# yksb.net
KiCad netlist of a schematic drawn in Altium Designer
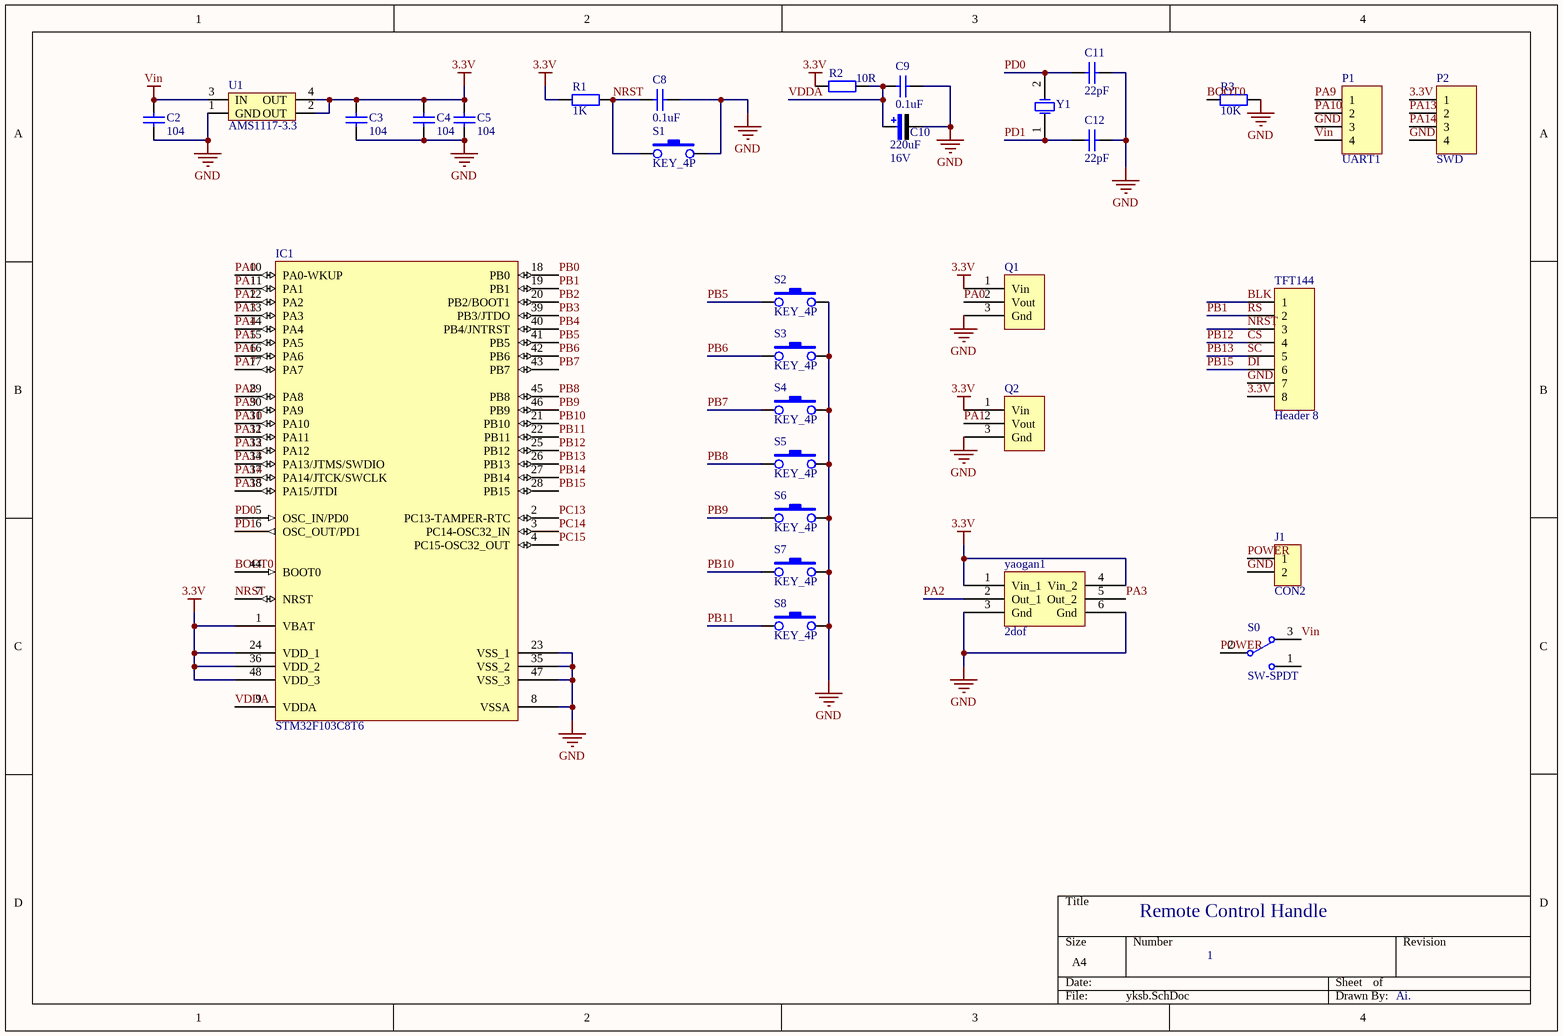
[diagram p0: yksb.SchDoc]

(export (version "E")
  (design (tool "Eeschema 10.0.6"))
  (components
    (comp (ref "C2")
      (value "104")
      (footprint "C-RAD-0603")
      (description "无极性电容")
      (fields (field (name "Comment") "Cap") (field (name "PUBLISHER") "Altium Limited"))
      (libsource (lib "Fszhang") (part "Cap"))
    )
    (comp (ref "C3")
      (value "104")
      (footprint "C-RAD-0603")
      (description "无极性电容")
      (fields (field (name "Comment") "Cap") (field (name "PUBLISHER") "Altium Limited"))
      (libsource (lib "Fszhang") (part "Cap"))
    )
    (comp (ref "C4")
      (value "104")
      (footprint "C-RAD-0603")
      (description "无极性电容")
      (fields (field (name "Comment") "Cap") (field (name "PUBLISHER") "Altium Limited"))
      (libsource (lib "Fszhang") (part "Cap"))
    )
    (comp (ref "C5")
      (value "104")
      (footprint "C-RAD-0603")
      (description "无极性电容")
      (fields (field (name "Comment") "Cap") (field (name "PUBLISHER") "Altium Limited"))
      (libsource (lib "Fszhang") (part "Cap"))
    )
    (comp (ref "C8")
      (value "0.1uF")
      (footprint "C-RAD-0603")
      (description "无极性电容")
      (fields (field (name "Comment") "Cap") (field (name "PUBLISHER") "Altium Limited"))
      (libsource (lib "Fszhang") (part "Cap"))
    )
    (comp (ref "C9")
      (value "0.1uF")
      (footprint "C-RAD-0603")
      (description "无极性电容")
      (fields (field (name "Comment") "Cap") (field (name "PUBLISHER") "Altium Limited"))
      (libsource (lib "Fszhang") (part "Cap"))
    )
    (comp (ref "C10")
      (value "220uF")
      (footprint "C-RB-S6")
      (description "极性电解电容")
      (fields
        (field (name "VOL") "16V")
        (field (name "Comment") "Cap Pol")
        (field (name "PUBLISHER") "Altium Limited")
      )
      (libsource (lib "Fszhang") (part "Cap Pol"))
    )
    (comp (ref "C11")
      (value "22pF")
      (footprint "C-RAD-0603")
      (description "无极性电容")
      (fields (field (name "Comment") "Cap") (field (name "PUBLISHER") "Altium Limited"))
      (libsource (lib "Fszhang") (part "Cap"))
    )
    (comp (ref "C12")
      (value "22pF")
      (footprint "C-RAD-0603")
      (description "无极性电容")
      (fields (field (name "Comment") "Cap") (field (name "PUBLISHER") "Altium Limited"))
      (libsource (lib "Fszhang") (part "Cap"))
    )
    (comp (ref "IC1")
      (value "STM32F103C8T6")
      (footprint "LQFP48_M")
      (description "单片机")
      (fields (field (name "PUBLISHER") "Altium Limited"))
      (libsource (lib "Chip") (part "STM32F103C8T6"))
    )
    (comp (ref "J1")
      (value "CON2")
      (footprint "DC-005")
      (description "连接器")
      (libsource (lib "Connector") (part "CON2"))
    )
    (comp (ref "P1")
      (value "UART1")
      (footprint "HDR1X4")
      (description "Header, 4-Pin")
      (fields (field (name "PUBLISHER") "Altium Limited"))
      (libsource (lib "Miscellaneous Connectors") (part "Header 4"))
    )
    (comp (ref "P2")
      (value "SWD")
      (footprint "HDR1X4")
      (description "Header, 4-Pin")
      (fields (field (name "PUBLISHER") "Altium Limited"))
      (libsource (lib "Miscellaneous Connectors") (part "Header 4"))
    )
    (comp (ref "Q1") (value "~") (footprint "dianweiqi") (libsource (lib "yaogan1") (part "dianweiqi")))
    (comp (ref "Q2") (value "~") (footprint "dianweiqi") (libsource (lib "yaogan1") (part "dianweiqi")))
    (comp (ref "R1")
      (value "1K")
      (footprint "0603-1")
      (description "贴片电阻")
      (fields (field (name "Comment") "Res1") (field (name "PUBLISHER") "Altium Limited"))
      (libsource (lib "Fszhang") (part "Res1"))
    )
    (comp (ref "R2")
      (value "10R")
      (footprint "0603-1")
      (description "贴片电阻")
      (fields (field (name "Comment") "Res1") (field (name "PUBLISHER") "Altium Limited"))
      (libsource (lib "Fszhang") (part "Res1"))
    )
    (comp (ref "R3")
      (value "10K")
      (footprint "0603-1")
      (description "贴片电阻")
      (fields (field (name "Comment") "Res1") (field (name "PUBLISHER") "Altium Limited"))
      (libsource (lib "Fszhang") (part "Res1"))
    )
    (comp (ref "S0")
      (value "SW-SPDT")
      (footprint "SWITCH_A2")
      (description "开关")
      (fields (field (name "PUBLISHER") "Altium Limited"))
      (libsource (lib "Fszhang") (part "SW-SPDT"))
    )
    (comp (ref "S1")
      (value "KEY_4P")
      (footprint "KEY_M")
      (description "轻触按键4P")
      (libsource (lib "Component") (part "KEY_4P"))
    )
    (comp (ref "S2")
      (value "KEY_4P")
      (footprint "KEY_M")
      (description "轻触按键4P")
      (libsource (lib "Component") (part "KEY_4P"))
    )
    (comp (ref "S3")
      (value "KEY_4P")
      (footprint "KEY_M")
      (description "轻触按键4P")
      (libsource (lib "Component") (part "KEY_4P"))
    )
    (comp (ref "S4")
      (value "KEY_4P")
      (footprint "KEY_M")
      (description "轻触按键4P")
      (libsource (lib "Component") (part "KEY_4P"))
    )
    (comp (ref "S5")
      (value "KEY_4P")
      (footprint "KEY_M")
      (description "轻触按键4P")
      (libsource (lib "Component") (part "KEY_4P"))
    )
    (comp (ref "S6")
      (value "KEY_4P")
      (footprint "KEY_M")
      (description "轻触按键4P")
      (libsource (lib "Component") (part "KEY_4P"))
    )
    (comp (ref "S7")
      (value "KEY_4P")
      (footprint "KEY_M")
      (description "轻触按键4P")
      (libsource (lib "Component") (part "KEY_4P"))
    )
    (comp (ref "S8")
      (value "KEY_4P")
      (footprint "KEY_M")
      (description "轻触按键4P")
      (libsource (lib "Component") (part "KEY_4P"))
    )
    (comp (ref "TFT144")
      (value "Header 8")
      (footprint "HDR1X8")
      (description "Header, 8-Pin")
      (fields (field (name "PUBLISHER") "Altium Limited"))
      (libsource (lib "Miscellaneous Connectors") (part "Header 8"))
    )
    (comp (ref "U1")
      (value "AMS1117-3.3")
      (footprint "AMS1117")
      (libsource (lib "MiniSTM32 V3.0封装库") (part "AMS1117"))
    )
    (comp (ref "Y1")
      (value "XTAL")
      (footprint "XTAL_US")
      (description "Crystal Oscillator")
      (fields (field (name "PUBLISHER") "*"))
      (libsource (lib "MiniSTM32底板_SCH (1)") (part "XTAL"))
    )
    (comp (ref "yaogan1") (value "2dof") (footprint "yaogan1") (libsource (lib "yaogan1") (part "yaogan1")))
  )
  (nets
    (net (code "1") (name "/BLK") (class "Default")
      (node (ref "TFT144") (pin "1") (pinfunction "1_1") (pintype "passive"))
    )
    (net (code "2") (name "/BOOT0") (class "Default")
      (node (ref "IC1") (pin "44") (pinfunction "BOOT0_44") (pintype "input"))
      (node (ref "R3") (pin "1") (pinfunction "1_1") (pintype "passive"))
    )
    (net (code "3") (name "/CS") (class "Default")
      (node (ref "IC1") (pin "25") (pinfunction "PB12_25") (pintype "bidirectional"))
      (node (ref "TFT144") (pin "4") (pinfunction "4_4") (pintype "passive"))
    )
    (net (code "4") (name "/DI") (class "Default")
      (node (ref "IC1") (pin "28") (pinfunction "PB15_28") (pintype "bidirectional"))
      (node (ref "TFT144") (pin "6") (pinfunction "6_6") (pintype "passive"))
    )
    (net (code "5") (name "/NRST") (class "Default")
      (node (ref "C8") (pin "2") (pinfunction "2_2") (pintype "passive"))
      (node (ref "IC1") (pin "7") (pinfunction "NRST_7") (pintype "bidirectional"))
      (node (ref "R1") (pin "2") (pinfunction "2_2") (pintype "passive"))
      (node (ref "S1") (pin "1") (pinfunction "1_1") (pintype "passive"))
      (node (ref "TFT144") (pin "3") (pinfunction "3_3") (pintype "passive"))
    )
    (net (code "6") (name "/PA0") (class "Default")
      (node (ref "IC1") (pin "10") (pinfunction "PA0-WKUP_10") (pintype "bidirectional"))
      (node (ref "Q1") (pin "2") (pinfunction "Vout_2") (pintype "passive"))
    )
    (net (code "7") (name "/PA1") (class "Default")
      (node (ref "IC1") (pin "11") (pinfunction "PA1_11") (pintype "bidirectional"))
      (node (ref "Q2") (pin "2") (pinfunction "Vout_2") (pintype "passive"))
    )
    (net (code "8") (name "/PA2") (class "Default")
      (node (ref "IC1") (pin "12") (pinfunction "PA2_12") (pintype "bidirectional"))
      (node (ref "yaogan1") (pin "2") (pinfunction "Out_1_2") (pintype "passive"))
    )
    (net (code "9") (name "/PA3") (class "Default")
      (node (ref "IC1") (pin "13") (pinfunction "PA3_13") (pintype "bidirectional"))
      (node (ref "yaogan1") (pin "5") (pinfunction "Out_2_5") (pintype "passive"))
    )
    (net (code "10") (name "/PA4") (class "Default")
      (node (ref "IC1") (pin "14") (pinfunction "PA4_14") (pintype "bidirectional"))
    )
    (net (code "11") (name "/PA5") (class "Default")
      (node (ref "IC1") (pin "15") (pinfunction "PA5_15") (pintype "bidirectional"))
    )
    (net (code "12") (name "/PA6") (class "Default")
      (node (ref "IC1") (pin "16") (pinfunction "PA6_16") (pintype "bidirectional"))
    )
    (net (code "13") (name "/PA7") (class "Default")
      (node (ref "IC1") (pin "17") (pinfunction "PA7_17") (pintype "bidirectional"))
    )
    (net (code "14") (name "/PA8") (class "Default")
      (node (ref "IC1") (pin "29") (pinfunction "PA8_29") (pintype "bidirectional"))
    )
    (net (code "15") (name "/PA9") (class "Default")
      (node (ref "IC1") (pin "30") (pinfunction "PA9_30") (pintype "bidirectional"))
      (node (ref "P1") (pin "1") (pinfunction "1_1") (pintype "passive"))
    )
    (net (code "16") (name "/PA10") (class "Default")
      (node (ref "IC1") (pin "31") (pinfunction "PA10_31") (pintype "bidirectional"))
      (node (ref "P1") (pin "2") (pinfunction "2_2") (pintype "passive"))
    )
    (net (code "17") (name "/PA11") (class "Default")
      (node (ref "IC1") (pin "32") (pinfunction "PA11_32") (pintype "bidirectional"))
    )
    (net (code "18") (name "/PA12") (class "Default")
      (node (ref "IC1") (pin "33") (pinfunction "PA12_33") (pintype "bidirectional"))
    )
    (net (code "19") (name "/PA13") (class "Default")
      (node (ref "IC1") (pin "34") (pinfunction "PA13/JTMS/SWDIO_34") (pintype "bidirectional"))
      (node (ref "P2") (pin "2") (pinfunction "2_2") (pintype "passive"))
    )
    (net (code "20") (name "/PA14") (class "Default")
      (node (ref "IC1") (pin "37") (pinfunction "PA14/JTCK/SWCLK_37") (pintype "bidirectional"))
      (node (ref "P2") (pin "3") (pinfunction "3_3") (pintype "passive"))
    )
    (net (code "21") (name "/PA15") (class "Default")
      (node (ref "IC1") (pin "38") (pinfunction "PA15/JTDI_38") (pintype "bidirectional"))
    )
    (net (code "22") (name "/PB0") (class "Default")
      (node (ref "IC1") (pin "18") (pinfunction "PB0_18") (pintype "bidirectional"))
    )
    (net (code "23") (name "/PB1") (class "Default")
      (node (ref "IC1") (pin "19") (pinfunction "PB1_19") (pintype "bidirectional"))
      (node (ref "TFT144") (pin "2") (pinfunction "2_2") (pintype "passive"))
    )
    (net (code "24") (name "/PB2") (class "Default")
      (node (ref "IC1") (pin "20") (pinfunction "PB2/BOOT1_20") (pintype "bidirectional"))
    )
    (net (code "25") (name "/PB3") (class "Default")
      (node (ref "IC1") (pin "39") (pinfunction "PB3/JTDO_39") (pintype "bidirectional"))
    )
    (net (code "26") (name "/PB4") (class "Default")
      (node (ref "IC1") (pin "40") (pinfunction "PB4/JNTRST_40") (pintype "bidirectional"))
    )
    (net (code "27") (name "/PB5") (class "Default")
      (node (ref "IC1") (pin "41") (pinfunction "PB5_41") (pintype "bidirectional"))
      (node (ref "S2") (pin "1") (pinfunction "1_1") (pintype "passive"))
    )
    (net (code "28") (name "/PB6") (class "Default")
      (node (ref "IC1") (pin "42") (pinfunction "PB6_42") (pintype "bidirectional"))
      (node (ref "S3") (pin "1") (pinfunction "1_1") (pintype "passive"))
    )
    (net (code "29") (name "/PB7") (class "Default")
      (node (ref "IC1") (pin "43") (pinfunction "PB7_43") (pintype "bidirectional"))
      (node (ref "S4") (pin "1") (pinfunction "1_1") (pintype "passive"))
    )
    (net (code "30") (name "/PB8") (class "Default")
      (node (ref "IC1") (pin "45") (pinfunction "PB8_45") (pintype "bidirectional"))
      (node (ref "S5") (pin "1") (pinfunction "1_1") (pintype "passive"))
    )
    (net (code "31") (name "/PB9") (class "Default")
      (node (ref "IC1") (pin "46") (pinfunction "PB9_46") (pintype "bidirectional"))
      (node (ref "S6") (pin "1") (pinfunction "1_1") (pintype "passive"))
    )
    (net (code "32") (name "/PB10") (class "Default")
      (node (ref "IC1") (pin "21") (pinfunction "PB10_21") (pintype "bidirectional"))
      (node (ref "S7") (pin "1") (pinfunction "1_1") (pintype "passive"))
    )
    (net (code "33") (name "/PB11") (class "Default")
      (node (ref "IC1") (pin "22") (pinfunction "PB11_22") (pintype "bidirectional"))
      (node (ref "S8") (pin "1") (pinfunction "1_1") (pintype "passive"))
    )
    (net (code "34") (name "/PB13") (class "Default")
      (node (ref "IC1") (pin "26") (pinfunction "PB13_26") (pintype "bidirectional"))
      (node (ref "TFT144") (pin "5") (pinfunction "5_5") (pintype "passive"))
    )
    (net (code "35") (name "/PB14") (class "Default")
      (node (ref "IC1") (pin "27") (pinfunction "PB14_27") (pintype "bidirectional"))
    )
    (net (code "36") (name "/PC13") (class "Default")
      (node (ref "IC1") (pin "2") (pinfunction "PC13-TAMPER-RTC_2") (pintype "bidirectional"))
    )
    (net (code "37") (name "/PC14") (class "Default")
      (node (ref "IC1") (pin "3") (pinfunction "PC14-OSC32_IN_3") (pintype "bidirectional"))
    )
    (net (code "38") (name "/PC15") (class "Default")
      (node (ref "IC1") (pin "4") (pinfunction "PC15-OSC32_OUT_4") (pintype "bidirectional"))
    )
    (net (code "39") (name "/PD0") (class "Default")
      (node (ref "C11") (pin "1") (pinfunction "1_1") (pintype "passive"))
      (node (ref "IC1") (pin "5") (pinfunction "OSC_IN/PD0_5") (pintype "input"))
      (node (ref "Y1") (pin "2") (pinfunction "OSC2_2") (pintype "passive"))
    )
    (net (code "40") (name "/PD1") (class "Default")
      (node (ref "C12") (pin "1") (pinfunction "1_1") (pintype "passive"))
      (node (ref "IC1") (pin "6") (pinfunction "OSC_OUT/PD1_6") (pintype "output"))
      (node (ref "Y1") (pin "1") (pinfunction "OSC1_1") (pintype "passive"))
    )
    (net (code "41") (name "/POWER") (class "Default")
      (node (ref "J1") (pin "1") (pinfunction "1_1") (pintype "passive"))
      (node (ref "S0") (pin "2") (pinfunction "2_2") (pintype "passive"))
    )
    (net (code "42") (name "/VDDA") (class "Default")
      (node (ref "C10") (pin "1") (pinfunction "1_1") (pintype "passive"))
      (node (ref "C9") (pin "2") (pinfunction "2_2") (pintype "passive"))
      (node (ref "IC1") (pin "9") (pinfunction "VDDA_9") (pintype "power_in"))
      (node (ref "R2") (pin "2") (pinfunction "2_2") (pintype "passive"))
    )
    (net (code "43") (name "3.3V") (class "Default")
      (node (ref "C3") (pin "1") (pinfunction "1_1") (pintype "passive"))
      (node (ref "C4") (pin "1") (pinfunction "1_1") (pintype "passive"))
      (node (ref "C5") (pin "1") (pinfunction "1_1") (pintype "passive"))
      (node (ref "IC1") (pin "1") (pinfunction "VBAT_1") (pintype "power_in"))
      (node (ref "IC1") (pin "24") (pinfunction "VDD_1_24") (pintype "power_in"))
      (node (ref "IC1") (pin "36") (pinfunction "VDD_2_36") (pintype "power_in"))
      (node (ref "IC1") (pin "48") (pinfunction "VDD_3_48") (pintype "power_in"))
      (node (ref "P2") (pin "1") (pinfunction "1_1") (pintype "passive"))
      (node (ref "Q1") (pin "1") (pinfunction "Vin_1") (pintype "passive"))
      (node (ref "Q2") (pin "1") (pinfunction "Vin_1") (pintype "passive"))
      (node (ref "R1") (pin "1") (pinfunction "1_1") (pintype "passive"))
      (node (ref "R2") (pin "1") (pinfunction "1_1") (pintype "passive"))
      (node (ref "TFT144") (pin "8") (pinfunction "8_8") (pintype "passive"))
      (node (ref "U1") (pin "2") (pinfunction "OUT_2") (pintype "passive"))
      (node (ref "U1") (pin "4") (pinfunction "OUT_4") (pintype "passive"))
      (node (ref "yaogan1") (pin "1") (pinfunction "Vin_1_1") (pintype "passive"))
      (node (ref "yaogan1") (pin "4") (pinfunction "Vin_2_4") (pintype "passive"))
    )
    (net (code "44") (name "GND") (class "Default")
      (node (ref "C10") (pin "2") (pinfunction "2_2") (pintype "passive"))
      (node (ref "C11") (pin "2") (pinfunction "2_2") (pintype "passive"))
      (node (ref "C12") (pin "2") (pinfunction "2_2") (pintype "passive"))
      (node (ref "C2") (pin "2") (pinfunction "2_2") (pintype "passive"))
      (node (ref "C3") (pin "2") (pinfunction "2_2") (pintype "passive"))
      (node (ref "C4") (pin "2") (pinfunction "2_2") (pintype "passive"))
      (node (ref "C5") (pin "2") (pinfunction "2_2") (pintype "passive"))
      (node (ref "C8") (pin "1") (pinfunction "1_1") (pintype "passive"))
      (node (ref "C9") (pin "1") (pinfunction "1_1") (pintype "passive"))
      (node (ref "IC1") (pin "23") (pinfunction "VSS_1_23") (pintype "power_in"))
      (node (ref "IC1") (pin "35") (pinfunction "VSS_2_35") (pintype "power_in"))
      (node (ref "IC1") (pin "47") (pinfunction "VSS_3_47") (pintype "power_in"))
      (node (ref "IC1") (pin "8") (pinfunction "VSSA_8") (pintype "power_in"))
      (node (ref "J1") (pin "2") (pinfunction "2_2") (pintype "passive"))
      (node (ref "P1") (pin "3") (pinfunction "3_3") (pintype "passive"))
      (node (ref "P2") (pin "4") (pinfunction "4_4") (pintype "passive"))
      (node (ref "Q1") (pin "3") (pinfunction "Gnd_3") (pintype "passive"))
      (node (ref "Q2") (pin "3") (pinfunction "Gnd_3") (pintype "passive"))
      (node (ref "R3") (pin "2") (pinfunction "2_2") (pintype "passive"))
      (node (ref "S1") (pin "2") (pinfunction "2_2") (pintype "passive"))
      (node (ref "S2") (pin "2") (pinfunction "2_2") (pintype "passive"))
      (node (ref "S3") (pin "2") (pinfunction "2_2") (pintype "passive"))
      (node (ref "S4") (pin "2") (pinfunction "2_2") (pintype "passive"))
      (node (ref "S5") (pin "2") (pinfunction "2_2") (pintype "passive"))
      (node (ref "S6") (pin "2") (pinfunction "2_2") (pintype "passive"))
      (node (ref "S7") (pin "2") (pinfunction "2_2") (pintype "passive"))
      (node (ref "S8") (pin "2") (pinfunction "2_2") (pintype "passive"))
      (node (ref "TFT144") (pin "7") (pinfunction "7_7") (pintype "passive"))
      (node (ref "U1") (pin "1") (pinfunction "GND_1") (pintype "passive"))
      (node (ref "yaogan1") (pin "3") (pinfunction "Gnd_3") (pintype "passive"))
      (node (ref "yaogan1") (pin "6") (pinfunction "Gnd_6") (pintype "passive"))
    )
    (net (code "45") (name "Vin") (class "Default")
      (node (ref "C2") (pin "1") (pinfunction "1_1") (pintype "passive"))
      (node (ref "P1") (pin "4") (pinfunction "4_4") (pintype "passive"))
      (node (ref "S0") (pin "3") (pinfunction "3_3") (pintype "passive"))
      (node (ref "U1") (pin "3") (pinfunction "IN_3") (pintype "passive"))
    )
    (net (code "46") (name "unconnected-(S0-Pad1)") (class "Default")
      (node (ref "S0") (pin "1") (pinfunction "1_1") (pintype "passive"))
    )
  )
)
